# SchemaGroupie.net
KiCad netlist of a schematic drawn in Altium Designer
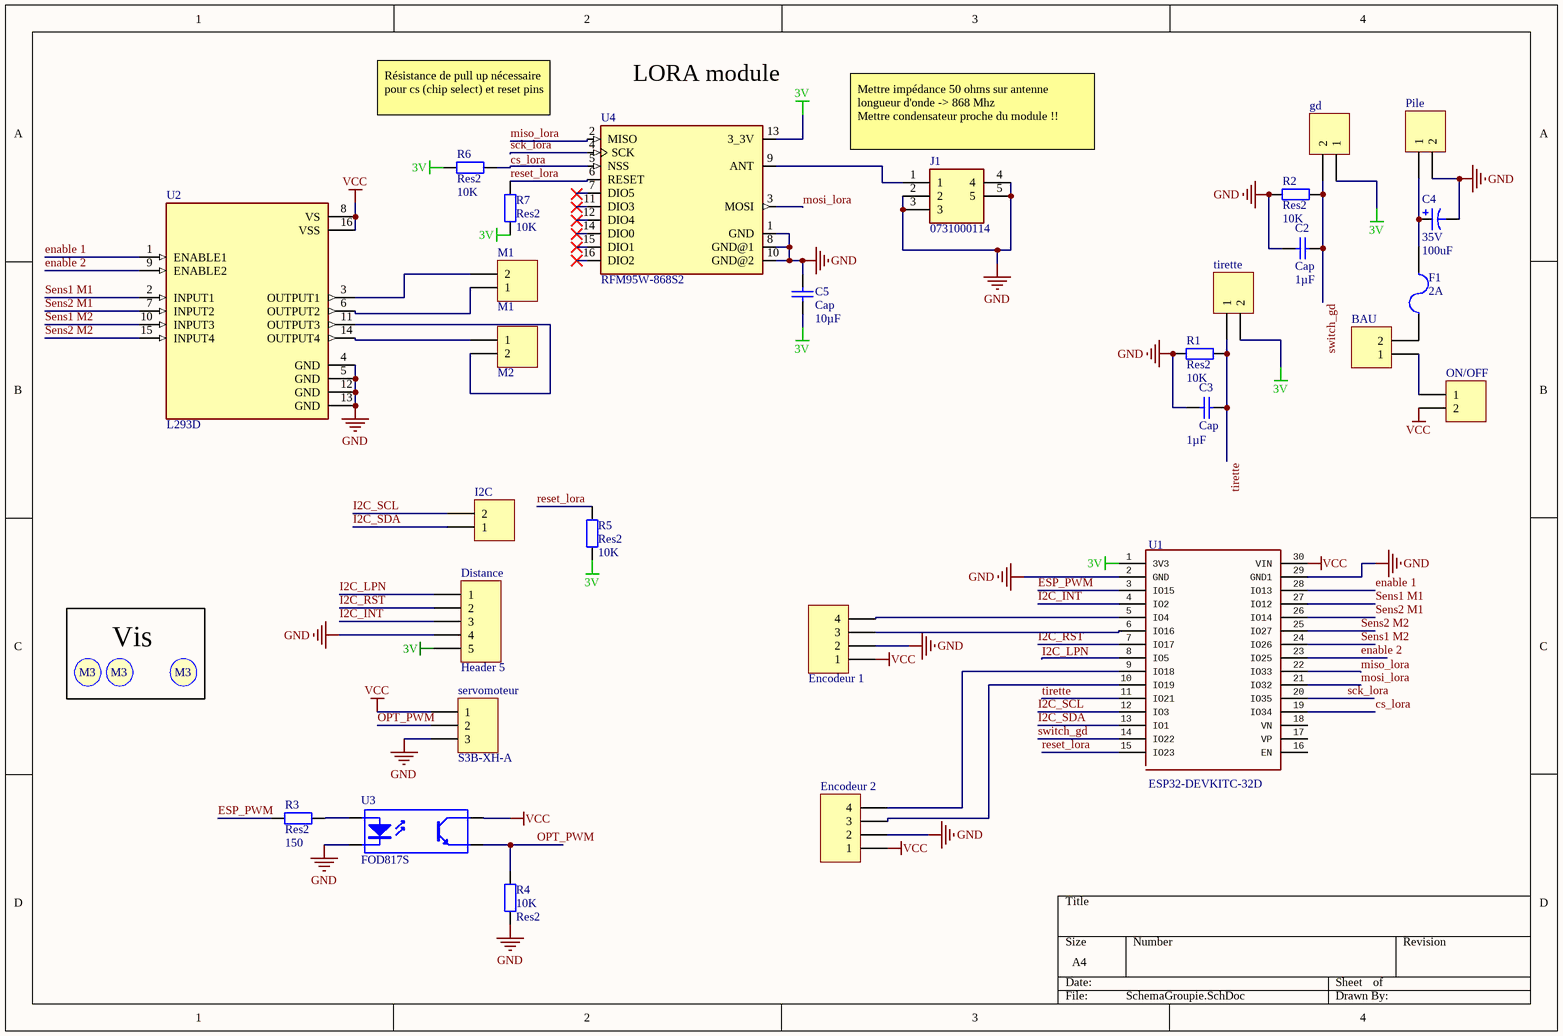
[diagram p0: SchemaGroupie.SchDoc]

(export (version "E")
  (design (tool "Eeschema 10.0.6"))
  (components
    (comp (ref "BAU")
      (value "~")
      (footprint "S2B-XH-A")
      (description "Header, 2-Pin, Right Angle")
      (fields (field (name "PUBLISHER") "Altium Limited"))
      (libsource (lib "") (part "Header 2H_2"))
    )
    (comp (ref "C2")
      (value "Cap")
      (footprint "Capacitor 1206")
      (description "Capacitor")
      (fields (field (name "ALTIUM_VALUE") "1µF") (field (name "PUBLISHER") "Altium Limited"))
      (libsource (lib "Miscellaneous Devices") (part "Cap"))
    )
    (comp (ref "C3")
      (value "Cap")
      (footprint "Capacitor 1206")
      (description "Capacitor")
      (fields (field (name "ALTIUM_VALUE") "1µF") (field (name "PUBLISHER") "Altium Limited"))
      (libsource (lib "Miscellaneous Devices") (part "Cap"))
    )
    (comp (ref "C4")
      (value "35V")
      (footprint "Condensateur")
      (description "Polarized Capacitor (Radial)")
      (fields (field (name "ALTIUM_VALUE") "100uF") (field (name "PUBLISHER") "Altium Limited"))
      (libsource (lib "Miscellaneous Devices") (part "Cap Pol1"))
    )
    (comp (ref "C5")
      (value "Cap")
      (footprint "Capacitor 1206")
      (description "Capacitor")
      (fields (field (name "ALTIUM_VALUE") "10µF") (field (name "PUBLISHER") "Altium Limited"))
      (libsource (lib "Miscellaneous Devices") (part "Cap"))
    )
    (comp (ref "Distance")
      (value "Header 5")
      (footprint "B5BXHAMLFSN")
      (description "Header, 5-Pin")
      (fields (field (name "PUBLISHER") "Altium Limited"))
      (libsource (lib "Miscellaneous Connectors") (part "Header 5"))
    )
    (comp (ref "Encodeur 1")
      (value "~")
      (footprint "B4BXHALFSN")
      (description "Header, 4-Pin, Right Angle")
      (fields (field (name "PUBLISHER") "Altium Limited"))
      (libsource (lib "Miscellaneous Connectors") (part "Header 4H"))
    )
    (comp (ref "Encodeur 2")
      (value "~")
      (footprint "B4BXHALFSN")
      (description "Header, 4-Pin, Right Angle")
      (fields (field (name "PUBLISHER") "Altium Limited"))
      (libsource (lib "Miscellaneous Connectors") (part "Header 4H"))
    )
    (comp (ref "F1")
      (value "2A")
      (footprint "Fuse")
      (description "Fuse")
      (fields (field (name "PUBLISHER") "Altium Limited"))
      (libsource (lib "Miscellaneous Devices") (part "Fuse 2"))
    )
    (comp (ref "gd")
      (value "~")
      (footprint "S2B-XH-A")
      (description "Header, 2-Pin, Right Angle")
      (fields (field (name "PUBLISHER") "Altium Limited"))
      (libsource (lib "") (part "Header 2H_1"))
    )
    (comp (ref "I2C")
      (value "~")
      (footprint "S2B-XH-A")
      (description "Header, 2-Pin, Right Angle")
      (fields (field (name "PUBLISHER") "Altium Limited"))
      (libsource (lib "Miscellaneous Connectors") (part "Header 2H"))
    )
    (comp (ref "J1")
      (value "0731000114")
      (footprint "0731000114")
      (description "Connector")
      (libsource (lib "*") (part "0731000114"))
    )
    (comp (ref "M1")
      (value "M1")
      (footprint "S2B-XH-A")
      (description "Header, 2-Pin, Right Angle")
      (fields (field (name "PUBLISHER") "Altium Limited"))
      (libsource (lib "Miscellaneous Connectors") (part "Header 2H"))
    )
    (comp (ref "M2")
      (value "M2")
      (footprint "S2B-XH-A")
      (description "Header, 2-Pin, Right Angle")
      (fields (field (name "PUBLISHER") "Altium Limited"))
      (libsource (lib "") (part "Header 2H_1"))
    )
    (comp (ref "ON/OFF")
      (value "~")
      (footprint "S2B-XH-A")
      (description "Header, 2-Pin, Right Angle")
      (fields (field (name "PUBLISHER") "Altium Limited"))
      (libsource (lib "") (part "Header 2H_1"))
    )
    (comp (ref "Pile")
      (value "~")
      (footprint "S2B-XH-A")
      (description "Header, 2-Pin, Right Angle")
      (fields (field (name "PUBLISHER") "Altium Limited"))
      (libsource (lib "Miscellaneous Connectors") (part "Header 2H"))
    )
    (comp (ref "R1")
      (value "Res2")
      (footprint "Resistor 1206")
      (description "Resistor")
      (fields (field (name "ALTIUM_VALUE") "10K") (field (name "PUBLISHER") "Altium Limited"))
      (libsource (lib "Miscellaneous Devices") (part "Res2"))
    )
    (comp (ref "R2")
      (value "Res2")
      (footprint "Resistor 1206")
      (description "Resistor")
      (fields (field (name "ALTIUM_VALUE") "10K") (field (name "PUBLISHER") "Altium Limited"))
      (libsource (lib "Miscellaneous Devices") (part "Res2"))
    )
    (comp (ref "R3")
      (value "Res2")
      (footprint "Resistor 1206")
      (description "Resistor")
      (fields (field (name "ALTIUM_VALUE") "150") (field (name "PUBLISHER") "Altium Limited"))
      (libsource (lib "Miscellaneous Devices") (part "Res2"))
    )
    (comp (ref "R4")
      (value "Res2")
      (footprint "Resistor 1206")
      (description "Resistor")
      (fields (field (name "ALTIUM_VALUE") "10K") (field (name "PUBLISHER") "Altium Limited"))
      (libsource (lib "") (part "Res2_1"))
    )
    (comp (ref "R5")
      (value "Res2")
      (footprint "Resistor 1206")
      (description "Resistor")
      (fields (field (name "ALTIUM_VALUE") "10K") (field (name "PUBLISHER") "Altium Limited"))
      (libsource (lib "") (part "Res2_1"))
    )
    (comp (ref "R6")
      (value "Res2")
      (footprint "Resistor 1206")
      (description "Resistor")
      (fields (field (name "ALTIUM_VALUE") "10K") (field (name "PUBLISHER") "Altium Limited"))
      (libsource (lib "Miscellaneous Devices") (part "Res2"))
    )
    (comp (ref "R7")
      (value "Res2")
      (footprint "Resistor 1206")
      (description "Resistor")
      (fields (field (name "ALTIUM_VALUE") "10K") (field (name "PUBLISHER") "Altium Limited"))
      (libsource (lib "") (part "Res2_1"))
    )
    (comp (ref "S1")
      (value "Screw M3")
      (footprint "Screw M3")
      (libsource (lib "Robot_2019") (part "Screw M3"))
    )
    (comp (ref "S2")
      (value "Screw M3")
      (footprint "Screw M3")
      (libsource (lib "Robot_2019") (part "Screw M3"))
    )
    (comp (ref "S4")
      (value "Screw M3")
      (footprint "Screw M3")
      (libsource (lib "Robot_2019") (part "Screw M3"))
    )
    (comp (ref "servomoteur")
      (value "S3B-XH-A")
      (footprint "S3B-XH-A")
      (description "Header, 3-Pin, Right Angle")
      (fields (field (name "PUBLISHER") "Altium Limited"))
      (libsource (lib "Miscellaneous Connectors") (part "Header 3H"))
    )
    (comp (ref "tirette")
      (value "~")
      (footprint "S2B-XH-A")
      (description "Header, 2-Pin, Right Angle")
      (fields (field (name "PUBLISHER") "Altium Limited"))
      (libsource (lib "Miscellaneous Connectors") (part "Header 2H"))
    )
    (comp (ref "U1")
      (value "ESP32-DEVKITC-32D")
      (footprint "MODULE_ESP32-DEVKITV1")
      (description "Eval Board For Esp-Wroom-32")
      (fields (field (name "MF") "Espressif Systems"))
      (libsource (lib "AltiumLibraryDDT") (part "ESP32-DEVKITC-32D"))
    )
    (comp (ref "U2")
      (value "L293D")
      (footprint "DIP880W50P254L2000H510Q16")
      (description "Bipolar Motor Driver - Parallel 16-PowerDIP")
      (fields (field (name "MF") "STMicroelectronics"))
      (libsource (lib "L293D") (part "L293D"))
    )
    (comp (ref "U3")
      (value "FOD817S")
      (footprint "SOP254P1016X385-4N")
      (description "4-Pin Phototransistor Optocoupler")
      (fields (field (name "PUBLISHER") "Altium Limited"))
      (libsource (lib "Miscellaneous Devices") (part "Optoisolator1"))
    )
    (comp (ref "U4")
      (value "RFM95W-868S2")
      (footprint "XCVR_RFM95W-868S2")
      (description "General ISM < 1GHz LoRaâ„¢ Transceiver Module 868MHz Antenna Not Included Surface Mount")
      (fields (field (name "MF") "RF"))
      (libsource (lib "LORA_RFM95W-868S2") (part "RFM95W-868S2"))
    )
  )
  (nets
    (net (code "1") (name "/ESP_PWM") (class "Default")
      (node (ref "R3") (pin "1") (pinfunction "1_1") (pintype "passive"))
      (node (ref "U1") (pin "3") (pinfunction "IO15_3") (pintype "passive"))
    )
    (net (code "2") (name "/I2C_INT") (class "Default")
      (node (ref "Distance") (pin "3") (pinfunction "3_3") (pintype "passive"))
      (node (ref "U1") (pin "4") (pinfunction "IO2_4") (pintype "passive"))
    )
    (net (code "3") (name "/I2C_LPN") (class "Default")
      (node (ref "Distance") (pin "1") (pinfunction "1_1") (pintype "passive"))
      (node (ref "U1") (pin "8") (pinfunction "IO5_8") (pintype "passive"))
    )
    (net (code "4") (name "/I2C_RST") (class "Default")
      (node (ref "Distance") (pin "2") (pinfunction "2_2") (pintype "passive"))
      (node (ref "U1") (pin "7") (pinfunction "IO17_7") (pintype "passive"))
    )
    (net (code "5") (name "/I2C_SCL") (class "Default")
      (node (ref "I2C") (pin "2") (pinfunction "2_2") (pintype "passive"))
      (node (ref "U1") (pin "12") (pinfunction "IO3_12") (pintype "passive"))
    )
    (net (code "6") (name "/I2C_SDA") (class "Default")
      (node (ref "I2C") (pin "1") (pinfunction "1_1") (pintype "passive"))
      (node (ref "U1") (pin "13") (pinfunction "IO1_13") (pintype "passive"))
    )
    (net (code "7") (name "/OPT_PWM") (class "Default")
      (node (ref "R4") (pin "2") (pinfunction "2_2") (pintype "passive"))
      (node (ref "U3") (pin "3") (pinfunction "E_3") (pintype "passive"))
      (node (ref "servomoteur") (pin "2") (pinfunction "2_2") (pintype "passive"))
    )
    (net (code "8") (name "/Sens1 M1") (class "Default")
      (node (ref "U1") (pin "27") (pinfunction "IO12_27") (pintype "passive"))
      (node (ref "U2") (pin "2") (pinfunction "INPUT1_2") (pintype "input"))
    )
    (net (code "9") (name "/Sens1 M2") (class "Default")
      (node (ref "U1") (pin "24") (pinfunction "IO26_24") (pintype "passive"))
      (node (ref "U2") (pin "10") (pinfunction "INPUT3_10") (pintype "input"))
    )
    (net (code "10") (name "/Sens2 M1") (class "Default")
      (node (ref "U1") (pin "26") (pinfunction "IO14_26") (pintype "passive"))
      (node (ref "U2") (pin "7") (pinfunction "INPUT2_7") (pintype "input"))
    )
    (net (code "11") (name "/Sens2 M2") (class "Default")
      (node (ref "U1") (pin "25") (pinfunction "IO27_25") (pintype "passive"))
      (node (ref "U2") (pin "15") (pinfunction "INPUT4_15") (pintype "input"))
    )
    (net (code "12") (name "/cs_lora") (class "Default")
      (node (ref "R6") (pin "2") (pinfunction "2_2") (pintype "passive"))
      (node (ref "U1") (pin "19") (pinfunction "IO34_19") (pintype "passive"))
      (node (ref "U4") (pin "5") (pinfunction "NSS_5") (pintype "input"))
    )
    (net (code "13") (name "/enable 1") (class "Default")
      (node (ref "U1") (pin "28") (pinfunction "IO13_28") (pintype "passive"))
      (node (ref "U2") (pin "1") (pinfunction "ENABLE1_1") (pintype "input"))
    )
    (net (code "14") (name "/enable 2") (class "Default")
      (node (ref "U1") (pin "23") (pinfunction "IO25_23") (pintype "passive"))
      (node (ref "U2") (pin "9") (pinfunction "ENABLE2_9") (pintype "input"))
    )
    (net (code "15") (name "/miso_lora") (class "Default")
      (node (ref "U1") (pin "22") (pinfunction "IO33_22") (pintype "passive"))
      (node (ref "U4") (pin "2") (pinfunction "MISO_2") (pintype "input"))
    )
    (net (code "16") (name "/mosi_lora") (class "Default")
      (node (ref "U1") (pin "21") (pinfunction "IO32_21") (pintype "passive"))
      (node (ref "U4") (pin "3") (pinfunction "MOSI_3") (pintype "output"))
    )
    (net (code "17") (name "/reset_lora") (class "Default")
      (node (ref "R5") (pin "2") (pinfunction "2_2") (pintype "passive"))
      (node (ref "R7") (pin "2") (pinfunction "2_2") (pintype "passive"))
      (node (ref "U1") (pin "15") (pinfunction "IO23_15") (pintype "passive"))
      (node (ref "U4") (pin "6") (pinfunction "RESET_6") (pintype "bidirectional"))
    )
    (net (code "18") (name "/sck_lora") (class "Default")
      (node (ref "U1") (pin "20") (pinfunction "IO35_20") (pintype "passive"))
      (node (ref "U4") (pin "4") (pinfunction "SCK_4") (pintype "input"))
    )
    (net (code "19") (name "/switch_gd") (class "Default")
      (node (ref "C2") (pin "2") (pinfunction "2_2") (pintype "passive"))
      (node (ref "R2") (pin "2") (pinfunction "2_2") (pintype "passive"))
      (node (ref "U1") (pin "14") (pinfunction "IO22_14") (pintype "passive"))
      (node (ref "gd") (pin "2") (pinfunction "2_2") (pintype "passive"))
    )
    (net (code "20") (name "/tirette") (class "Default")
      (node (ref "C3") (pin "2") (pinfunction "2_2") (pintype "passive"))
      (node (ref "R1") (pin "2") (pinfunction "2_2") (pintype "passive"))
      (node (ref "U1") (pin "11") (pinfunction "IO21_11") (pintype "passive"))
      (node (ref "tirette") (pin "1") (pinfunction "1_1") (pintype "passive"))
    )
    (net (code "21") (name "3V") (class "Default")
      (node (ref "C5") (pin "1") (pinfunction "1_1") (pintype "passive"))
      (node (ref "Distance") (pin "5") (pinfunction "5_5") (pintype "passive"))
      (node (ref "R5") (pin "1") (pinfunction "1_1") (pintype "passive"))
      (node (ref "R6") (pin "1") (pinfunction "1_1") (pintype "passive"))
      (node (ref "R7") (pin "1") (pinfunction "1_1") (pintype "passive"))
      (node (ref "U1") (pin "1") (pinfunction "3V3_1") (pintype "passive"))
      (node (ref "U4") (pin "13") (pinfunction "3_3V_13") (pintype "power_in"))
      (node (ref "gd") (pin "1") (pinfunction "1_1") (pintype "passive"))
      (node (ref "tirette") (pin "2") (pinfunction "2_2") (pintype "passive"))
    )
    (net (code "22") (name "GND") (class "Default")
      (node (ref "C2") (pin "1") (pinfunction "1_1") (pintype "passive"))
      (node (ref "C3") (pin "1") (pinfunction "1_1") (pintype "passive"))
      (node (ref "C4") (pin "2") (pinfunction "2_2") (pintype "passive"))
      (node (ref "C5") (pin "2") (pinfunction "2_2") (pintype "passive"))
      (node (ref "Distance") (pin "4") (pinfunction "4_4") (pintype "passive"))
      (node (ref "Encodeur 1") (pin "2") (pinfunction "2_2") (pintype "passive"))
      (node (ref "Encodeur 2") (pin "2") (pinfunction "2_2") (pintype "passive"))
      (node (ref "J1") (pin "2") (pinfunction "2_2") (pintype "passive"))
      (node (ref "J1") (pin "3") (pinfunction "3_3") (pintype "passive"))
      (node (ref "J1") (pin "4") (pinfunction "4_4") (pintype "passive"))
      (node (ref "J1") (pin "5") (pinfunction "5_5") (pintype "passive"))
      (node (ref "Pile") (pin "2") (pinfunction "2_2") (pintype "passive"))
      (node (ref "R1") (pin "1") (pinfunction "1_1") (pintype "passive"))
      (node (ref "R2") (pin "1") (pinfunction "1_1") (pintype "passive"))
      (node (ref "R4") (pin "1") (pinfunction "1_1") (pintype "passive"))
      (node (ref "U1") (pin "2") (pinfunction "GND_2") (pintype "passive"))
      (node (ref "U1") (pin "29") (pinfunction "GND1_29") (pintype "passive"))
      (node (ref "U2") (pin "12") (pinfunction "GND_12") (pintype "power_in"))
      (node (ref "U2") (pin "13") (pinfunction "GND_13") (pintype "power_in"))
      (node (ref "U2") (pin "4") (pinfunction "GND_4") (pintype "power_in"))
      (node (ref "U2") (pin "5") (pinfunction "GND_5") (pintype "power_in"))
      (node (ref "U3") (pin "2") (pinfunction "K_2") (pintype "passive"))
      (node (ref "U4") (pin "1") (pinfunction "GND_1") (pintype "power_in"))
      (node (ref "U4") (pin "10") (pinfunction "GND@2_10") (pintype "power_in"))
      (node (ref "U4") (pin "8") (pinfunction "GND@1_8") (pintype "power_in"))
      (node (ref "servomoteur") (pin "3") (pinfunction "3_3") (pintype "passive"))
    )
    (net (code "23") (name "Net-(BAU-Pad1)") (class "Default")
      (node (ref "BAU") (pin "1") (pinfunction "1_1") (pintype "passive"))
      (node (ref "ON/OFF") (pin "1") (pinfunction "1_1") (pintype "passive"))
    )
    (net (code "24") (name "Net-(BAU-Pad2)") (class "Default")
      (node (ref "BAU") (pin "2") (pinfunction "2_2") (pintype "passive"))
      (node (ref "F1") (pin "1") (pinfunction "1_1") (pintype "passive"))
    )
    (net (code "25") (name "Net-(C4-Pad1)") (class "Default")
      (node (ref "C4") (pin "1") (pinfunction "1_1") (pintype "passive"))
      (node (ref "F1") (pin "2") (pinfunction "2_2") (pintype "passive"))
      (node (ref "Pile") (pin "1") (pinfunction "1_1") (pintype "passive"))
    )
    (net (code "26") (name "Net-(U1-IO4)") (class "Default")
      (node (ref "Encodeur 1") (pin "4") (pinfunction "4_4") (pintype "passive"))
      (node (ref "U1") (pin "5") (pinfunction "IO4_5") (pintype "passive"))
    )
    (net (code "27") (name "Net-(U1-IO16)") (class "Default")
      (node (ref "Encodeur 1") (pin "3") (pinfunction "3_3") (pintype "passive"))
      (node (ref "U1") (pin "6") (pinfunction "IO16_6") (pintype "passive"))
    )
    (net (code "28") (name "Net-(U1-IO18)") (class "Default")
      (node (ref "Encodeur 2") (pin "4") (pinfunction "4_4") (pintype "passive"))
      (node (ref "U1") (pin "9") (pinfunction "IO18_9") (pintype "passive"))
    )
    (net (code "29") (name "Net-(U1-IO19)") (class "Default")
      (node (ref "Encodeur 2") (pin "3") (pinfunction "3_3") (pintype "passive"))
      (node (ref "U1") (pin "10") (pinfunction "IO19_10") (pintype "passive"))
    )
    (net (code "30") (name "Net-(U2-OUTPUT1)") (class "Default")
      (node (ref "M1") (pin "2") (pinfunction "2_2") (pintype "passive"))
      (node (ref "U2") (pin "3") (pinfunction "OUTPUT1_3") (pintype "output"))
    )
    (net (code "31") (name "Net-(U2-OUTPUT2)") (class "Default")
      (node (ref "M1") (pin "1") (pinfunction "1_1") (pintype "passive"))
      (node (ref "U2") (pin "6") (pinfunction "OUTPUT2_6") (pintype "output"))
    )
    (net (code "32") (name "Net-(U2-OUTPUT3)") (class "Default")
      (node (ref "M2") (pin "2") (pinfunction "2_2") (pintype "passive"))
      (node (ref "U2") (pin "11") (pinfunction "OUTPUT3_11") (pintype "output"))
    )
    (net (code "33") (name "Net-(U2-OUTPUT4)") (class "Default")
      (node (ref "M2") (pin "1") (pinfunction "1_1") (pintype "passive"))
      (node (ref "U2") (pin "14") (pinfunction "OUTPUT4_14") (pintype "output"))
    )
    (net (code "34") (name "Net-(U3-A)") (class "Default")
      (node (ref "R3") (pin "2") (pinfunction "2_2") (pintype "passive"))
      (node (ref "U3") (pin "1") (pinfunction "A_1") (pintype "passive"))
    )
    (net (code "35") (name "Net-(U4-ANT)") (class "Default")
      (node (ref "J1") (pin "1") (pinfunction "1_1") (pintype "passive"))
      (node (ref "U4") (pin "9") (pinfunction "ANT_9") (pintype "passive"))
    )
    (net (code "36") (name "VCC") (class "Default")
      (node (ref "Encodeur 1") (pin "1") (pinfunction "1_1") (pintype "passive"))
      (node (ref "Encodeur 2") (pin "1") (pinfunction "1_1") (pintype "passive"))
      (node (ref "ON/OFF") (pin "2") (pinfunction "2_2") (pintype "passive"))
      (node (ref "U1") (pin "30") (pinfunction "VIN_30") (pintype "passive"))
      (node (ref "U2") (pin "16") (pinfunction "VSS_16") (pintype "power_in"))
      (node (ref "U2") (pin "8") (pinfunction "VS_8") (pintype "power_in"))
      (node (ref "U3") (pin "4") (pinfunction "C_4") (pintype "passive"))
      (node (ref "servomoteur") (pin "1") (pinfunction "1_1") (pintype "passive"))
    )
    (net (code "37") (name "unconnected-(U1-EN-Pad16)") (class "Default")
      (node (ref "U1") (pin "16") (pinfunction "EN_16") (pintype "passive"))
    )
    (net (code "38") (name "unconnected-(U1-VN-Pad18)") (class "Default")
      (node (ref "U1") (pin "18") (pinfunction "VN_18") (pintype "passive"))
    )
    (net (code "39") (name "unconnected-(U1-VP-Pad17)") (class "Default")
      (node (ref "U1") (pin "17") (pinfunction "VP_17") (pintype "passive"))
    )
    (net (code "40") (name "unconnected-(U4-DIO0-Pad14)") (class "Default")
      (node (ref "U4") (pin "14") (pinfunction "DIO0_14") (pintype "bidirectional+no_connect"))
    )
    (net (code "41") (name "unconnected-(U4-DIO1-Pad15)") (class "Default")
      (node (ref "U4") (pin "15") (pinfunction "DIO1_15") (pintype "bidirectional+no_connect"))
    )
    (net (code "42") (name "unconnected-(U4-DIO2-Pad16)") (class "Default")
      (node (ref "U4") (pin "16") (pinfunction "DIO2_16") (pintype "bidirectional+no_connect"))
    )
    (net (code "43") (name "unconnected-(U4-DIO3-Pad11)") (class "Default")
      (node (ref "U4") (pin "11") (pinfunction "DIO3_11") (pintype "bidirectional+no_connect"))
    )
    (net (code "44") (name "unconnected-(U4-DIO4-Pad12)") (class "Default")
      (node (ref "U4") (pin "12") (pinfunction "DIO4_12") (pintype "bidirectional+no_connect"))
    )
    (net (code "45") (name "unconnected-(U4-DIO5-Pad7)") (class "Default")
      (node (ref "U4") (pin "7") (pinfunction "DIO5_7") (pintype "bidirectional+no_connect"))
    )
  )
)
